# deadlocks.net
KiCad netlist of a schematic drawn in EAGLE
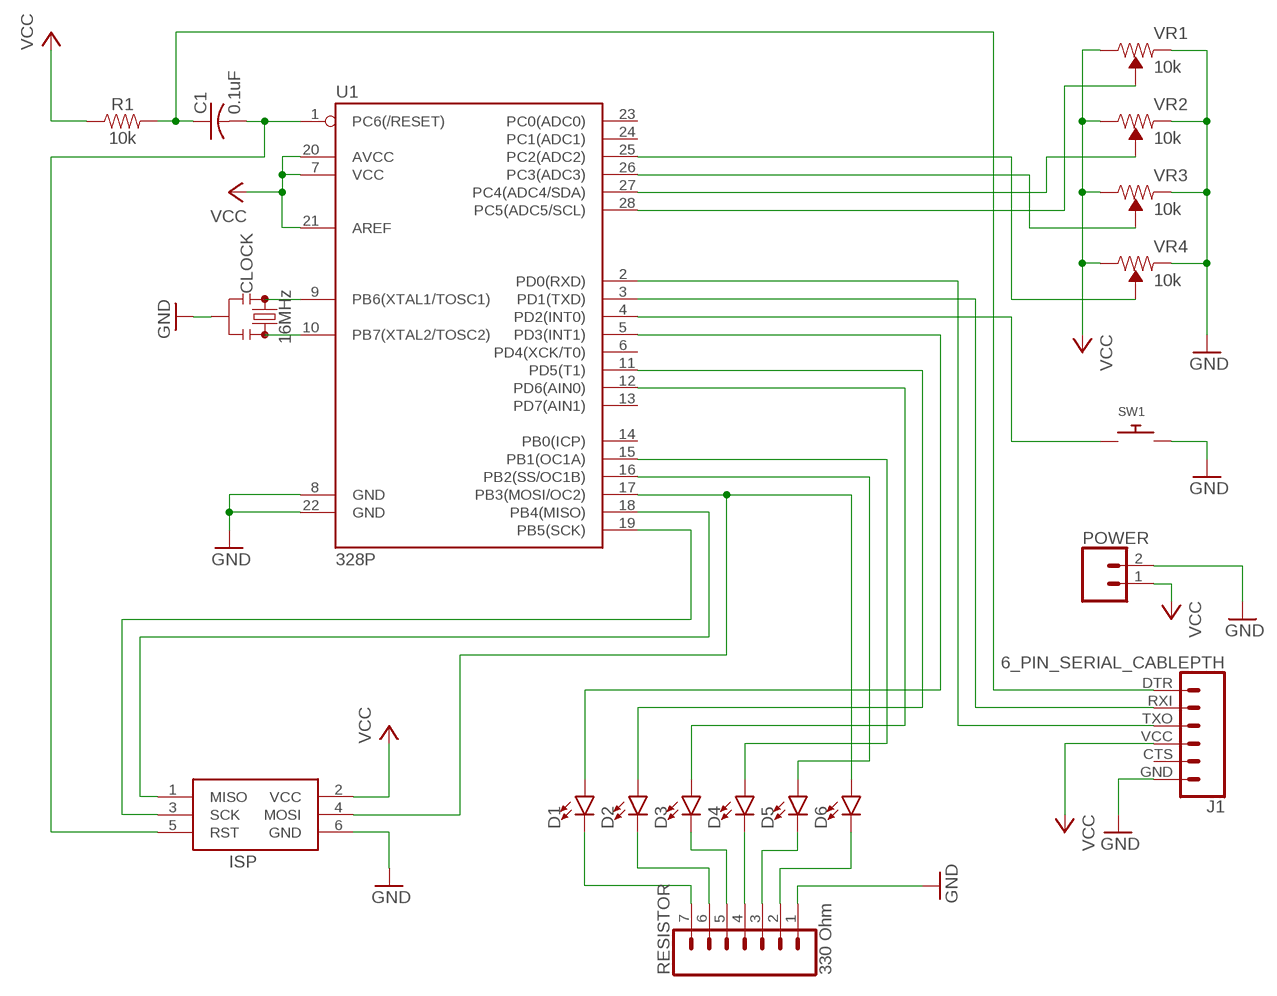
[diagram p0: schematic, sheet 1]

(export (version "E")
  (design (tool "Eeschema 10.0.6"))
  (components
    (comp (ref "C1")
      (value "0.1uF")
      (footprint "eagle-import:C025-024X044")
      (libsource (lib "eagle-import") (part "C-US025-024X044"))
    )
    (comp (ref "CLOCK")
      (value "16MHz")
      (footprint "eagle-import:RESONATOR-PTH-7.6X3.8")
      (libsource (lib "eagle-import") (part "RESONATORPTH-7.6X3.8"))
    )
    (comp (ref "D1")
      (value "LED5MM")
      (footprint "eagle-import:LED_5MM")
      (libsource (lib "eagle-import") (part "LED5MM"))
    )
    (comp (ref "D2")
      (value "LED5MM")
      (footprint "eagle-import:LED_5MM")
      (libsource (lib "eagle-import") (part "LED5MM"))
    )
    (comp (ref "D3")
      (value "LED5MM")
      (footprint "eagle-import:LED_5MM")
      (libsource (lib "eagle-import") (part "LED5MM"))
    )
    (comp (ref "D4")
      (value "LED5MM")
      (footprint "eagle-import:LED_5MM")
      (libsource (lib "eagle-import") (part "LED5MM"))
    )
    (comp (ref "D5")
      (value "LED5MM")
      (footprint "eagle-import:LED_5MM")
      (libsource (lib "eagle-import") (part "LED5MM"))
    )
    (comp (ref "D6")
      (value "LED5MM")
      (footprint "eagle-import:LED_5MM")
      (libsource (lib "eagle-import") (part "LED5MM"))
    )
    (comp (ref "ISP")
      (value "AVRISP-6")
      (footprint "eagle-import:AVRISP")
      (libsource (lib "eagle-import") (part "AVRISP-6"))
    )
    (comp (ref "J1")
      (value "6_PIN_SERIAL_CABLEPTH")
      (footprint "eagle-import:FTDI_BASIC")
      (libsource (lib "eagle-import") (part "6_PIN_SERIAL_CABLEPTH"))
    )
    (comp (ref "POWER")
      (value "CONN_02")
      (footprint "eagle-import:1X02")
      (libsource (lib "eagle-import") (part "CONN_02"))
    )
    (comp (ref "R1")
      (value "10k")
      (footprint "eagle-import:AXIAL-0.3")
      (libsource (lib "eagle-import") (part "10KOHM-HORIZ-1/4W-1%"))
    )
    (comp (ref "RESISTOR")
      (value "330 Ohm")
      (footprint "eagle-import:1X07")
      (libsource (lib "eagle-import") (part "CONN_07"))
    )
    (comp (ref "SW1")
      (value "SWITCH_PUSHBUTTONEVQ-PE")
      (footprint "eagle-import:TACT_PANA-EVQ")
      (libsource (lib "eagle-import") (part "SWITCH_PUSHBUTTONEVQ-PE"))
    )
    (comp (ref "U1")
      (value "328P")
      (footprint "eagle-import:DIP28")
      (libsource (lib "eagle-import") (part "ATMEGA328P_PDIP"))
    )
    (comp (ref "VR1")
      (value "10k")
      (footprint "eagle-import:TRIMPOT-PTH-3386U")
      (libsource (lib "eagle-import") (part "TRIMPOT-PTH-10MM-KNOB-1/2W-10%"))
    )
    (comp (ref "VR2")
      (value "10k")
      (footprint "eagle-import:TRIMPOT-PTH-3386U")
      (libsource (lib "eagle-import") (part "TRIMPOT-PTH-10MM-KNOB-1/2W-10%"))
    )
    (comp (ref "VR3")
      (value "10k")
      (footprint "eagle-import:TRIMPOT-PTH-3386U")
      (libsource (lib "eagle-import") (part "TRIMPOT-PTH-10MM-KNOB-1/2W-10%"))
    )
    (comp (ref "VR4")
      (value "10k")
      (footprint "eagle-import:TRIMPOT-PTH-3386U")
      (libsource (lib "eagle-import") (part "TRIMPOT-PTH-10MM-KNOB-1/2W-10%"))
    )
  )
  (nets
    (net (code "1") (name "GND") (class "Default")
      (node (ref "CLOCK") (pin "2") (pinfunction "2_2") (pintype "passive"))
      (node (ref "ISP") (pin "6") (pinfunction "GND_6") (pintype "power_in"))
      (node (ref "J1") (pin "GND") (pinfunction "6_GND") (pintype "passive"))
      (node (ref "POWER") (pin "2") (pinfunction "2_2") (pintype "passive"))
      (node (ref "RESISTOR") (pin "1") (pinfunction "1_1") (pintype "passive"))
      (node (ref "SW1") (pin "P$2") (pinfunction "P$2_P$2") (pintype "passive"))
      (node (ref "U1") (pin "22") (pinfunction "GND_22") (pintype "bidirectional"))
      (node (ref "U1") (pin "8") (pinfunction "GND_8") (pintype "bidirectional"))
      (node (ref "VR1") (pin "1") (pinfunction "CCW_1") (pintype "passive"))
      (node (ref "VR2") (pin "1") (pinfunction "CCW_1") (pintype "passive"))
      (node (ref "VR3") (pin "1") (pinfunction "CCW_1") (pintype "passive"))
      (node (ref "VR4") (pin "1") (pinfunction "CCW_1") (pintype "passive"))
    )
    (net (code "2") (name "Net-(D1-C)") (class "Default")
      (node (ref "D1") (pin "K") (pinfunction "C_K") (pintype "passive"))
      (node (ref "RESISTOR") (pin "7") (pinfunction "7_7") (pintype "passive"))
    )
    (net (code "3") (name "Net-(D2-C)") (class "Default")
      (node (ref "D2") (pin "K") (pinfunction "C_K") (pintype "passive"))
      (node (ref "RESISTOR") (pin "6") (pinfunction "6_6") (pintype "passive"))
    )
    (net (code "4") (name "Net-(D3-C)") (class "Default")
      (node (ref "D3") (pin "K") (pinfunction "C_K") (pintype "passive"))
      (node (ref "RESISTOR") (pin "5") (pinfunction "5_5") (pintype "passive"))
    )
    (net (code "5") (name "Net-(D4-C)") (class "Default")
      (node (ref "D4") (pin "K") (pinfunction "C_K") (pintype "passive"))
      (node (ref "RESISTOR") (pin "4") (pinfunction "4_4") (pintype "passive"))
    )
    (net (code "6") (name "Net-(D5-C)") (class "Default")
      (node (ref "D5") (pin "K") (pinfunction "C_K") (pintype "passive"))
      (node (ref "RESISTOR") (pin "3") (pinfunction "3_3") (pintype "passive"))
    )
    (net (code "7") (name "Net-(D6-C)") (class "Default")
      (node (ref "D6") (pin "K") (pinfunction "C_K") (pintype "passive"))
      (node (ref "RESISTOR") (pin "2") (pinfunction "2_2") (pintype "passive"))
    )
    (net (code "8") (name "Net-(ISP-MISO)") (class "Default")
      (node (ref "ISP") (pin "1") (pinfunction "MISO_1") (pintype "input"))
      (node (ref "U1") (pin "18") (pinfunction "PB4(MISO)_18") (pintype "bidirectional"))
    )
    (net (code "9") (name "Net-(ISP-MOSI)") (class "Default")
      (node (ref "D6") (pin "A") (pinfunction "A_A") (pintype "passive"))
      (node (ref "ISP") (pin "4") (pinfunction "MOSI_4") (pintype "output"))
      (node (ref "U1") (pin "17") (pinfunction "PB3(MOSI/OC2)_17") (pintype "bidirectional"))
    )
    (net (code "10") (name "Net-(ISP-RST)") (class "Default")
      (node (ref "C1") (pin "2") (pinfunction "2_2") (pintype "passive"))
      (node (ref "ISP") (pin "5") (pinfunction "RST_5") (pintype "output"))
      (node (ref "U1") (pin "1") (pinfunction "PC6(/RESET)_1") (pintype "bidirectional"))
    )
    (net (code "11") (name "Net-(ISP-SCK)") (class "Default")
      (node (ref "ISP") (pin "3") (pinfunction "SCK_3") (pintype "output"))
      (node (ref "U1") (pin "19") (pinfunction "PB5(SCK)_19") (pintype "bidirectional"))
    )
    (net (code "12") (name "Net-(J1-1)") (class "Default")
      (node (ref "C1") (pin "1") (pinfunction "1_1") (pintype "passive"))
      (node (ref "J1") (pin "DTR") (pinfunction "1_DTR") (pintype "passive"))
      (node (ref "R1") (pin "P$2") (pinfunction "2_P$2") (pintype "passive"))
    )
    (net (code "13") (name "Net-(J1-2)") (class "Default")
      (node (ref "J1") (pin "RXI") (pinfunction "2_RXI") (pintype "passive"))
      (node (ref "U1") (pin "3") (pinfunction "PD1(TXD)_3") (pintype "bidirectional"))
    )
    (net (code "14") (name "Net-(J1-3)") (class "Default")
      (node (ref "J1") (pin "TXO") (pinfunction "3_TXO") (pintype "passive"))
      (node (ref "U1") (pin "2") (pinfunction "PD0(RXD)_2") (pintype "bidirectional"))
    )
    (net (code "15") (name "Net-(U1-PB1(OC1A))") (class "Default")
      (node (ref "D4") (pin "A") (pinfunction "A_A") (pintype "passive"))
      (node (ref "U1") (pin "15") (pinfunction "PB1(OC1A)_15") (pintype "bidirectional"))
    )
    (net (code "16") (name "Net-(U1-PB2(SS{slash}OC1B))") (class "Default")
      (node (ref "D5") (pin "A") (pinfunction "A_A") (pintype "passive"))
      (node (ref "U1") (pin "16") (pinfunction "PB2(SS/OC1B)_16") (pintype "bidirectional"))
    )
    (net (code "17") (name "Net-(U1-PB6(XTAL1{slash}TOSC1))") (class "Default")
      (node (ref "CLOCK") (pin "1") (pinfunction "1_1") (pintype "passive"))
      (node (ref "U1") (pin "9") (pinfunction "PB6(XTAL1/TOSC1)_9") (pintype "bidirectional"))
    )
    (net (code "18") (name "Net-(U1-PB7(XTAL2{slash}TOSC2))") (class "Default")
      (node (ref "CLOCK") (pin "3") (pinfunction "3_3") (pintype "passive"))
      (node (ref "U1") (pin "10") (pinfunction "PB7(XTAL2/TOSC2)_10") (pintype "bidirectional"))
    )
    (net (code "19") (name "Net-(U1-PC2(ADC2))") (class "Default")
      (node (ref "U1") (pin "25") (pinfunction "PC2(ADC2)_25") (pintype "bidirectional"))
      (node (ref "VR4") (pin "2") (pinfunction "WIPER_2") (pintype "passive"))
    )
    (net (code "20") (name "Net-(U1-PC3(ADC3))") (class "Default")
      (node (ref "U1") (pin "26") (pinfunction "PC3(ADC3)_26") (pintype "bidirectional"))
      (node (ref "VR3") (pin "2") (pinfunction "WIPER_2") (pintype "passive"))
    )
    (net (code "21") (name "Net-(U1-PC4(ADC4{slash}SDA))") (class "Default")
      (node (ref "U1") (pin "27") (pinfunction "PC4(ADC4/SDA)_27") (pintype "bidirectional"))
      (node (ref "VR2") (pin "2") (pinfunction "WIPER_2") (pintype "passive"))
    )
    (net (code "22") (name "Net-(U1-PC5(ADC5{slash}SCL))") (class "Default")
      (node (ref "U1") (pin "28") (pinfunction "PC5(ADC5/SCL)_28") (pintype "bidirectional"))
      (node (ref "VR1") (pin "2") (pinfunction "WIPER_2") (pintype "passive"))
    )
    (net (code "23") (name "Net-(U1-PD2(INT0))") (class "Default")
      (node (ref "SW1") (pin "P$1") (pinfunction "P$1_P$1") (pintype "passive"))
      (node (ref "U1") (pin "4") (pinfunction "PD2(INT0)_4") (pintype "bidirectional"))
    )
    (net (code "24") (name "Net-(U1-PD3(INT1))") (class "Default")
      (node (ref "D1") (pin "A") (pinfunction "A_A") (pintype "passive"))
      (node (ref "U1") (pin "5") (pinfunction "PD3(INT1)_5") (pintype "bidirectional"))
    )
    (net (code "25") (name "Net-(U1-PD5(T1))") (class "Default")
      (node (ref "D2") (pin "A") (pinfunction "A_A") (pintype "passive"))
      (node (ref "U1") (pin "11") (pinfunction "PD5(T1)_11") (pintype "bidirectional"))
    )
    (net (code "26") (name "Net-(U1-PD6(AIN0))") (class "Default")
      (node (ref "D3") (pin "A") (pinfunction "A_A") (pintype "passive"))
      (node (ref "U1") (pin "12") (pinfunction "PD6(AIN0)_12") (pintype "bidirectional"))
    )
    (net (code "27") (name "VCC") (class "Default")
      (node (ref "ISP") (pin "2") (pinfunction "VCC_2") (pintype "power_in"))
      (node (ref "J1") (pin "VCC") (pinfunction "4_VCC") (pintype "passive"))
      (node (ref "POWER") (pin "1") (pinfunction "1_1") (pintype "passive"))
      (node (ref "R1") (pin "P$1") (pinfunction "1_P$1") (pintype "passive"))
      (node (ref "U1") (pin "20") (pinfunction "AVCC_20") (pintype "bidirectional"))
      (node (ref "U1") (pin "21") (pinfunction "AREF_21") (pintype "bidirectional"))
      (node (ref "U1") (pin "7") (pinfunction "VCC_7") (pintype "bidirectional"))
      (node (ref "VR1") (pin "3") (pinfunction "CW_3") (pintype "passive"))
      (node (ref "VR2") (pin "3") (pinfunction "CW_3") (pintype "passive"))
      (node (ref "VR3") (pin "3") (pinfunction "CW_3") (pintype "passive"))
      (node (ref "VR4") (pin "3") (pinfunction "CW_3") (pintype "passive"))
    )
    (net (code "28") (name "unconnected-(J1-5-PadCTS)") (class "Default")
      (node (ref "J1") (pin "CTS") (pinfunction "5_CTS") (pintype "passive"))
    )
    (net (code "29") (name "unconnected-(U1-PB0(ICP)-Pad14)") (class "Default")
      (node (ref "U1") (pin "14") (pinfunction "PB0(ICP)_14") (pintype "bidirectional"))
    )
    (net (code "30") (name "unconnected-(U1-PC0(ADC0)-Pad23)") (class "Default")
      (node (ref "U1") (pin "23") (pinfunction "PC0(ADC0)_23") (pintype "bidirectional"))
    )
    (net (code "31") (name "unconnected-(U1-PC1(ADC1)-Pad24)") (class "Default")
      (node (ref "U1") (pin "24") (pinfunction "PC1(ADC1)_24") (pintype "bidirectional"))
    )
    (net (code "32") (name "unconnected-(U1-PD4(XCK{slash}T0)-Pad6)") (class "Default")
      (node (ref "U1") (pin "6") (pinfunction "PD4(XCK/T0)_6") (pintype "bidirectional"))
    )
    (net (code "33") (name "unconnected-(U1-PD7(AIN1)-Pad13)") (class "Default")
      (node (ref "U1") (pin "13") (pinfunction "PD7(AIN1)_13") (pintype "bidirectional"))
    )
  )
)
